# Schematic_DevKit_ESP32.net
KiCad netlist of a schematic drawn in Altium Designer
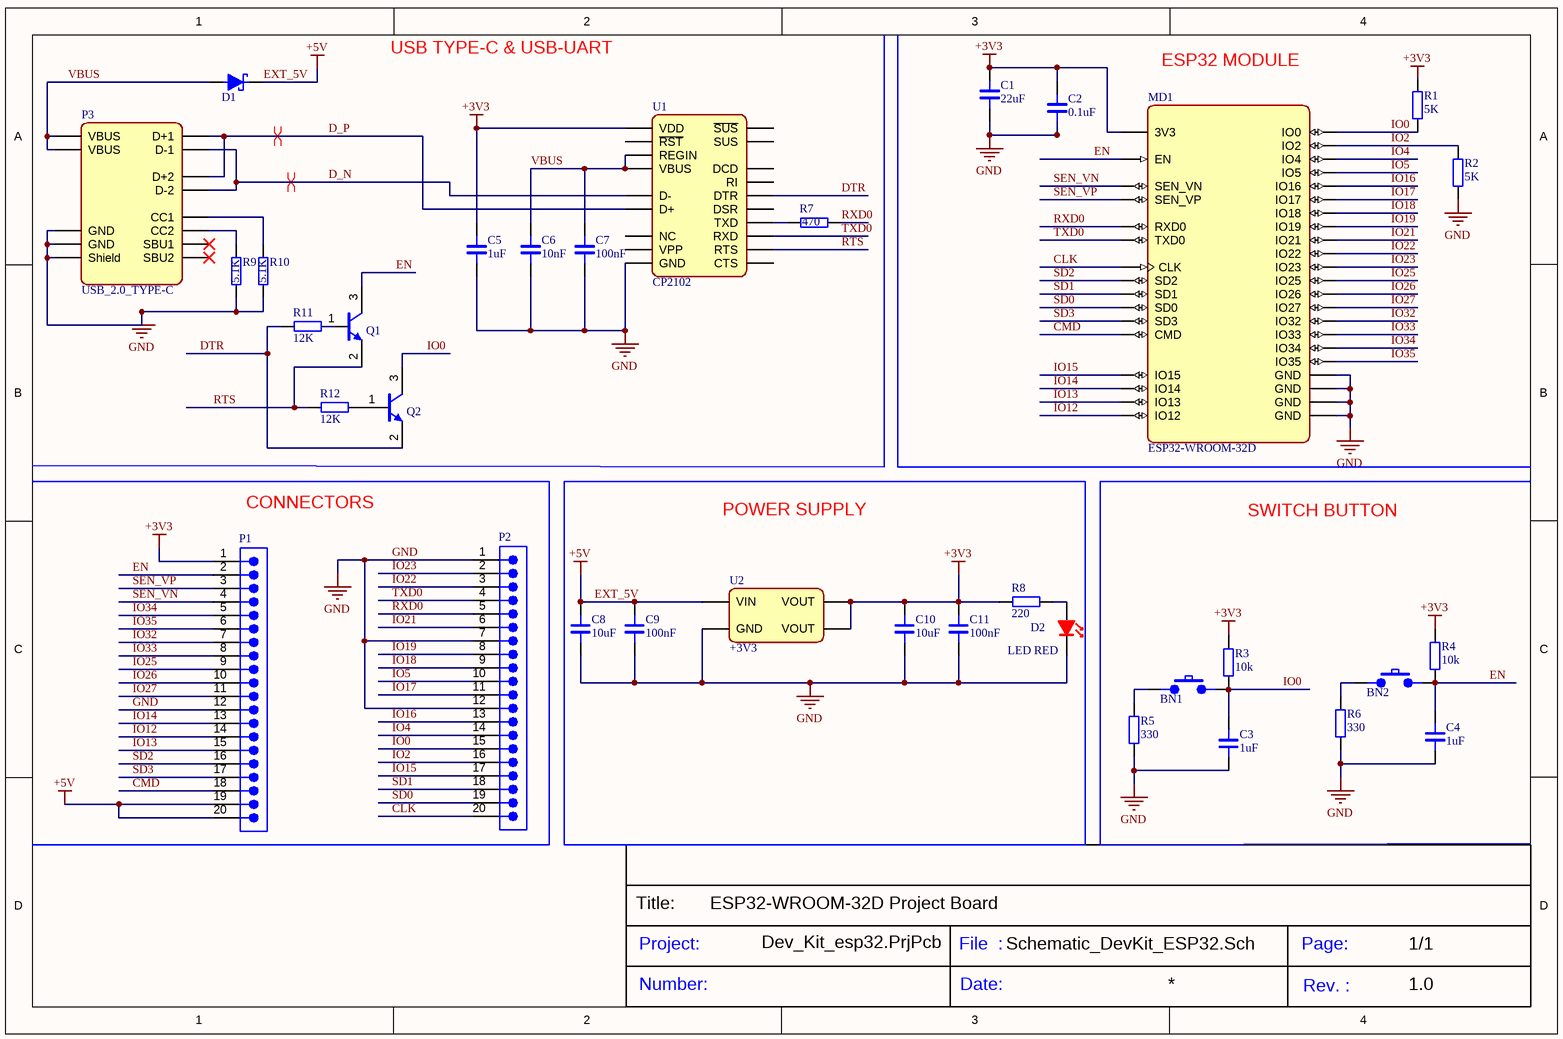
[diagram p0: Schematic_DevKit_ESP32.SchDoc]

(export (version "E")
  (design (tool "Eeschema 10.0.6"))
  (components
    (comp (ref "BN1")
      (value "SKRPABE010")
      (footprint "BTN_SKRPABE010")
      (description "3.2mm 2.5mm button 50mA Brick SPST 16V SMD Tactile Switches")
      (fields (field (name "JLCPCB PART") "?"))
      (libsource (lib "FIC_OAL") (part "BTN_SKRPABE010"))
    )
    (comp (ref "BN2")
      (value "SKRPABE010")
      (footprint "BTN_SKRPABE010")
      (description "3.2mm 2.5mm button 50mA Brick SPST 16V SMD Tactile Switches")
      (fields (field (name "JLCPCB PART") "?"))
      (libsource (lib "FIC_OAL") (part "BTN_SKRPABE010"))
    )
    (comp (ref "C1")
      (value "22uF")
      (footprint "CAP_0603")
      (description "0603 Multilayer Ceramic Capacitors MLCC - SMD/SMT ROHS")
      (fields (field (name "LCSC PART") "C86295") (field (name "JLCPCB PART") "?"))
      (libsource (lib "FIC_OAL") (part "CAP_0603"))
    )
    (comp (ref "C2")
      (value "0.1uF")
      (footprint "CAP_0603")
      (description "0603 Multilayer Ceramic Capacitors MLCC - SMD/SMT ROHS")
      (fields (field (name "LCSC PART") "C36911391") (field (name "JLCPCB PART") "?"))
      (libsource (lib "FIC_OAL") (part "CAP_0603"))
    )
    (comp (ref "C3")
      (value "1uF")
      (footprint "CAP_0603")
      (description "0603 Multilayer Ceramic Capacitors MLCC - SMD/SMT ROHS")
      (fields (field (name "LCSC PART") "C111590") (field (name "JLCPCB PART") "?"))
      (libsource (lib "FIC_OAL") (part "CAP_0603"))
    )
    (comp (ref "C4")
      (value "1uF")
      (footprint "CAP_0603")
      (description "0603 Multilayer Ceramic Capacitors MLCC - SMD/SMT ROHS")
      (fields (field (name "LCSC PART") "C111590") (field (name "JLCPCB PART") "?"))
      (libsource (lib "FIC_OAL") (part "CAP_0603"))
    )
    (comp (ref "C5")
      (value "1uF")
      (footprint "CAP_0603")
      (description "0603 Multilayer Ceramic Capacitors MLCC - SMD/SMT ROHS")
      (fields (field (name "LCSC PART") "C111590") (field (name "JLCPCB PART") "?"))
      (libsource (lib "FIC_OAL") (part "CAP_0603"))
    )
    (comp (ref "C6")
      (value "10nF")
      (footprint "CAP_0603")
      (description "0603 Multilayer Ceramic Capacitors MLCC - SMD/SMT ROHS")
      (fields (field (name "LCSC PART") "C36911415") (field (name "JLCPCB PART") "?"))
      (libsource (lib "FIC_OAL") (part "CAP_0603"))
    )
    (comp (ref "C7")
      (value "100nF")
      (footprint "CAP_0603")
      (description "0603 Multilayer Ceramic Capacitors MLCC - SMD/SMT ROHS")
      (fields (field (name "LCSC PART") "C519438") (field (name "JLCPCB PART") "?"))
      (libsource (lib "FIC_OAL") (part "CAP_0603"))
    )
    (comp (ref "C8")
      (value "10uF")
      (footprint "CAP_0603")
      (description "0603 Multilayer Ceramic Capacitors MLCC - SMD/SMT ROHS")
      (fields (field (name "LCSC PART") "C19702") (field (name "JLCPCB PART") "?"))
      (libsource (lib "FIC_OAL") (part "CAP_0603"))
    )
    (comp (ref "C9")
      (value "100nF")
      (footprint "CAP_0603")
      (description "0603 Multilayer Ceramic Capacitors MLCC - SMD/SMT ROHS")
      (fields (field (name "LCSC PART") "?"))
      (libsource (lib "FIC_OAL") (part "CAP_0603"))
    )
    (comp (ref "C10")
      (value "10uF")
      (footprint "CAP_0603")
      (description "0603 Multilayer Ceramic Capacitors MLCC - SMD/SMT ROHS")
      (fields (field (name "LCSC PART") "C19702") (field (name "JLCPCB PART") "?"))
      (libsource (lib "FIC_OAL") (part "CAP_0603"))
    )
    (comp (ref "C11")
      (value "100nF")
      (footprint "CAP_0603")
      (description "0603 Multilayer Ceramic Capacitors MLCC - SMD/SMT ROHS")
      (fields (field (name "LCSC PART") "?"))
      (libsource (lib "FIC_OAL") (part "CAP_0603"))
    )
    (comp (ref "D1")
      (value "SS34")
      (footprint "DIO_SMA")
      (description "40V 500mV@3A 3A SMC (SBD)")
      (fields (field (name "JLCPCB PART") "?") (field (name "LCSC PART") "C8678"))
      (libsource (lib "FIC_OAL") (part "DIO_SS34"))
    )
    (comp (ref "D2")
      (value "LED RED")
      (footprint "LED_RED_V0805")
      (description "20mA 615nm~630nm RED")
      (fields (field (name "JLCPCB PART") "?"))
      (libsource (lib "FIC_OAL") (part "LED_RED_V0805"))
    )
    (comp (ref "MD1")
      (value "ESP32-WROOM-32D")
      (footprint "MD_ESP32_WROOM_D")
      (description "core ESP32-D0WD, 32Mbits, 3.3V, 40Mhz, onboard antenna")
      (fields (field (name "MFR. PART") "ESP32-WROOM-32D-N4") (field (name "LCSC PART") "C473012"))
      (libsource (lib "FIC_OAL") (part "MD_ESP32_WROOM_D"))
    )
    (comp (ref "P1")
      (value "61302011121")
      (footprint "61302011121")
      (libsource (lib "Altium Content Vault") (part "Header_Male_1R_20P"))
    )
    (comp (ref "P2")
      (value "61302011121")
      (footprint "61302011121")
      (libsource (lib "Altium Content Vault") (part "Header_Male_1R_20P"))
    )
    (comp (ref "P3")
      (value "USB_2.0_TYPE-C")
      (footprint "CON_USB_2.0_TYPE-C")
      (description "USB Connectors USB Jack 2.0, Type-C, Horizontal SMT")
      (fields (field (name "MFR. PART") "GT-USB-7010ASV") (field (name "LCSC PART") "C2988369"))
      (libsource (lib "FIC_OAL") (part "CON_USB_2.0_TYPE-C"))
    )
    (comp (ref "Q1")
      (value "BC846x")
      (footprint "BJT_ BC846x")
      (description "Single Bipolar Transistor, NPN, 65 V, 100 mA, 250 mW, SOT23 (TO-236AB), 3 Pins, Surface Mount")
      (fields (field (name "MFR. PART") "BC846B") (field (name "LCSC PART") "C5338312"))
      (libsource (lib "FIC_OAL") (part "BJT_ BC846x"))
    )
    (comp (ref "Q2")
      (value "BC846x")
      (footprint "BJT_ BC846x")
      (description "Single Bipolar Transistor, NPN, 65 V, 100 mA, 250 mW, SOT23 (TO-236AB), 3 Pins, Surface Mount")
      (fields (field (name "MFR. PART") "BC846B") (field (name "LCSC PART") "C5338312"))
      (libsource (lib "FIC_OAL") (part "BJT_ BC846x"))
    )
    (comp (ref "R1")
      (value "5K")
      (footprint "RES_0603")
      (description "0603 Thick Film Resistor - Surface Mount ROHS")
      (fields (field (name "MFR. PART") "RTT035001FTP") (field (name "LCSC PART") "C166926"))
      (libsource (lib "FIC_OAL") (part "RES_0603"))
    )
    (comp (ref "R2")
      (value "5K")
      (footprint "RES_0603")
      (description "0603 Thick Film Resistor - Surface Mount ROHS")
      (fields (field (name "MFR. PART") "RTT035001FTP") (field (name "LCSC PART") "C166926"))
      (libsource (lib "FIC_OAL") (part "RES_0603"))
    )
    (comp (ref "R3")
      (value "10k")
      (footprint "RES_0603")
      (description "0603 Thick Film Resistor - Surface Mount ROHS")
      (fields (field (name "MFR. PART") "FRC0603J103 TS") (field (name "LCSC PART") "C2930027"))
      (libsource (lib "FIC_OAL") (part "RES_0603"))
    )
    (comp (ref "R4")
      (value "10k")
      (footprint "RES_0603")
      (description "0603 Thick Film Resistor - Surface Mount ROHS")
      (fields (field (name "MFR. PART") "FRC0603J103 TS") (field (name "LCSC PART") "C2930027"))
      (libsource (lib "FIC_OAL") (part "RES_0603"))
    )
    (comp (ref "R5")
      (value "330")
      (footprint "RES_0603")
      (description "0603 Thick Film Resistor - Surface Mount ROHS")
      (fields (field (name "MFR. PART") "0603WAJ0331T5E") (field (name "LCSC PART") "C25231"))
      (libsource (lib "FIC_OAL") (part "RES_0603"))
    )
    (comp (ref "R6")
      (value "330")
      (footprint "RES_0603")
      (description "0603 Thick Film Resistor - Surface Mount ROHS")
      (fields (field (name "MFR. PART") "?"))
      (libsource (lib "FIC_OAL") (part "RES_0603"))
    )
    (comp (ref "R7")
      (value "470")
      (footprint "RES_0603")
      (description "0603 Thick Film Resistor - Surface Mount ROHS")
      (fields (field (name "MFR. PART") "FRC0603F4700TS") (field (name "LCSC PART") "C2907041"))
      (libsource (lib "FIC_OAL") (part "RES_0603"))
    )
    (comp (ref "R8")
      (value "220")
      (footprint "RES_0603")
      (description "0603 Thick Film Resistor - Surface Mount ROHS")
      (fields (field (name "MFR. PART") "FRC0603F2200TS") (field (name "LCSC PART") "C2907014"))
      (libsource (lib "FIC_OAL") (part "RES_0603"))
    )
    (comp (ref "R9")
      (value "5.1K")
      (footprint "RES_0603")
      (description "0603 Thick Film Resistor - Surface Mount ROHS")
      (fields (field (name "MFR. PART") "FRC0603F5101TS") (field (name "LCSC PART") "C2907044"))
      (libsource (lib "FIC_OAL") (part "RES_0603"))
    )
    (comp (ref "R10")
      (value "5.1K")
      (footprint "RES_0603")
      (description "0603 Thick Film Resistor - Surface Mount ROHS")
      (fields (field (name "MFR. PART") "FRC0603F5101TS") (field (name "LCSC PART") "C2907044"))
      (libsource (lib "FIC_OAL") (part "RES_0603"))
    )
    (comp (ref "R11")
      (value "12K")
      (footprint "RES_0603")
      (description "0603 Thick Film Resistor - Surface Mount ROHS")
      (fields (field (name "MFR. PART") "FRC0603F1202TS") (field (name "LCSC PART") "C2906989"))
      (libsource (lib "FIC_OAL") (part "RES_0603"))
    )
    (comp (ref "R12")
      (value "12K")
      (footprint "RES_0603")
      (description "0603 Thick Film Resistor - Surface Mount ROHS")
      (fields (field (name "MFR. PART") "FRC0603F1202TS") (field (name "LCSC PART") "C2906989"))
      (libsource (lib "FIC_OAL") (part "RES_0603"))
    )
    (comp (ref "U1")
      (value "CP2102")
      (footprint "INF_CP2102")
      (description "USB to UART bridge USB 2.0 3.3V, CP2102-GMR, VFQFN-28")
      (fields (field (name "MFR. PART") "CP2102-GMR") (field (name "LCSC PART") "C6568"))
      (libsource (lib "FIC_OAL") (part "INF_CP2102"))
    )
    (comp (ref "U2")
      (value "+3V3")
      (footprint "PWR_LD1117_SOT223")
      (description "Linear Voltage Regulators (LDO)")
      (fields (field (name "MFR. PART") "LD1117-3.3") (field (name "LCSC PART") "C347229"))
      (libsource (lib "FIC_OAL") (part "PWR_LD1117"))
    )
  )
  (nets
    (net (code "1") (name "+3V3") (class "Default")
      (node (ref "C1") (pin "2") (pinfunction "2_2") (pintype "passive"))
      (node (ref "C10") (pin "2") (pinfunction "2_2") (pintype "passive"))
      (node (ref "C11") (pin "2") (pinfunction "2_2") (pintype "passive"))
      (node (ref "C2") (pin "2") (pinfunction "2_2") (pintype "passive"))
      (node (ref "C5") (pin "2") (pinfunction "2_2") (pintype "passive"))
      (node (ref "MD1") (pin "2") (pinfunction "3V3_2") (pintype "passive"))
      (node (ref "P1") (pin "1") (pinfunction "1_1") (pintype "passive"))
      (node (ref "R1") (pin "2") (pinfunction "2_2") (pintype "passive"))
      (node (ref "R3") (pin "2") (pinfunction "2_2") (pintype "passive"))
      (node (ref "R4") (pin "2") (pinfunction "2_2") (pintype "passive"))
      (node (ref "R8") (pin "1") (pinfunction "1_1") (pintype "passive"))
      (node (ref "U1") (pin "6") (pinfunction "VDD_6") (pintype "passive"))
      (node (ref "U2") (pin "2") (pinfunction "_VOUT_2") (pintype "passive"))
      (node (ref "U2") (pin "4") (pinfunction "VOUT_4") (pintype "passive"))
    )
    (net (code "2") (name "+5V") (class "Default")
      (node (ref "C8") (pin "2") (pinfunction "2_2") (pintype "passive"))
      (node (ref "C9") (pin "2") (pinfunction "2_2") (pintype "passive"))
      (node (ref "D1") (pin "C") (pinfunction "C_C") (pintype "passive"))
      (node (ref "P1") (pin "19") (pinfunction "19_19") (pintype "passive"))
      (node (ref "P1") (pin "20") (pinfunction "20_20") (pintype "passive"))
      (node (ref "U2") (pin "3") (pinfunction "VIN_3") (pintype "passive"))
    )
    (net (code "3") (name "/CLK") (class "Default")
      (node (ref "MD1") (pin "20") (pinfunction "CLK_20") (pintype "input"))
      (node (ref "P2") (pin "20") (pinfunction "20_20") (pintype "passive"))
    )
    (net (code "4") (name "/CMD") (class "Default")
      (node (ref "MD1") (pin "19") (pinfunction "CMD_19") (pintype "bidirectional"))
      (node (ref "P1") (pin "18") (pinfunction "18_18") (pintype "passive"))
    )
    (net (code "5") (name "/DTR") (class "Default")
      (node (ref "Q2") (pin "2") (pinfunction "E_2") (pintype "passive"))
      (node (ref "R11") (pin "1") (pinfunction "1_1") (pintype "passive"))
      (node (ref "U1") (pin "28") (pinfunction "DTR_28") (pintype "passive"))
    )
    (net (code "6") (name "/D_N") (class "Default")
      (node (ref "P3") (pin "A7") (pinfunction "D-1_A7") (pintype "passive"))
      (node (ref "P3") (pin "B7") (pinfunction "D-2_B7") (pintype "passive"))
      (node (ref "U1") (pin "5") (pinfunction "D-_5") (pintype "passive"))
    )
    (net (code "7") (name "/D_P") (class "Default")
      (node (ref "P3") (pin "A6") (pinfunction "D+1_A6") (pintype "passive"))
      (node (ref "P3") (pin "B6") (pinfunction "D+2_B6") (pintype "passive"))
      (node (ref "U1") (pin "4") (pinfunction "D+_4") (pintype "passive"))
    )
    (net (code "8") (name "/EN") (class "Default")
      (node (ref "BN2") (pin "34") (pinfunction "34_34") (pintype "passive"))
      (node (ref "C4") (pin "2") (pinfunction "2_2") (pintype "passive"))
      (node (ref "MD1") (pin "3") (pinfunction "EN_3") (pintype "input"))
      (node (ref "P1") (pin "2") (pinfunction "2_2") (pintype "passive"))
      (node (ref "Q1") (pin "3") (pinfunction "C_3") (pintype "passive"))
      (node (ref "R4") (pin "1") (pinfunction "1_1") (pintype "passive"))
    )
    (net (code "9") (name "/IO0") (class "Default")
      (node (ref "BN1") (pin "34") (pinfunction "34_34") (pintype "passive"))
      (node (ref "C3") (pin "2") (pinfunction "2_2") (pintype "passive"))
      (node (ref "MD1") (pin "25") (pinfunction "IO0_25") (pintype "bidirectional"))
      (node (ref "P2") (pin "15") (pinfunction "15_15") (pintype "passive"))
      (node (ref "Q2") (pin "3") (pinfunction "C_3") (pintype "passive"))
      (node (ref "R1") (pin "1") (pinfunction "1_1") (pintype "passive"))
      (node (ref "R3") (pin "1") (pinfunction "1_1") (pintype "passive"))
    )
    (net (code "10") (name "/IO2") (class "Default")
      (node (ref "MD1") (pin "24") (pinfunction "IO2_24") (pintype "bidirectional"))
      (node (ref "P2") (pin "16") (pinfunction "16_16") (pintype "passive"))
      (node (ref "R2") (pin "2") (pinfunction "2_2") (pintype "passive"))
    )
    (net (code "11") (name "/IO4") (class "Default")
      (node (ref "MD1") (pin "26") (pinfunction "IO4_26") (pintype "bidirectional"))
      (node (ref "P2") (pin "14") (pinfunction "14_14") (pintype "passive"))
    )
    (net (code "12") (name "/IO5") (class "Default")
      (node (ref "MD1") (pin "29") (pinfunction "IO5_29") (pintype "bidirectional"))
      (node (ref "P2") (pin "10") (pinfunction "10_10") (pintype "passive"))
    )
    (net (code "13") (name "/IO12") (class "Default")
      (node (ref "MD1") (pin "14") (pinfunction "IO12_14") (pintype "bidirectional"))
      (node (ref "P1") (pin "14") (pinfunction "14_14") (pintype "passive"))
    )
    (net (code "14") (name "/IO13") (class "Default")
      (node (ref "MD1") (pin "16") (pinfunction "IO13_16") (pintype "bidirectional"))
      (node (ref "P1") (pin "15") (pinfunction "15_15") (pintype "passive"))
    )
    (net (code "15") (name "/IO14") (class "Default")
      (node (ref "MD1") (pin "13") (pinfunction "IO14_13") (pintype "bidirectional"))
      (node (ref "P1") (pin "13") (pinfunction "13_13") (pintype "passive"))
    )
    (net (code "16") (name "/IO15") (class "Default")
      (node (ref "MD1") (pin "23") (pinfunction "IO15_23") (pintype "bidirectional"))
      (node (ref "P2") (pin "17") (pinfunction "17_17") (pintype "passive"))
    )
    (net (code "17") (name "/IO16") (class "Default")
      (node (ref "MD1") (pin "27") (pinfunction "IO16_27") (pintype "bidirectional"))
      (node (ref "P2") (pin "13") (pinfunction "13_13") (pintype "passive"))
    )
    (net (code "18") (name "/IO17") (class "Default")
      (node (ref "MD1") (pin "28") (pinfunction "IO17_28") (pintype "bidirectional"))
      (node (ref "P2") (pin "11") (pinfunction "11_11") (pintype "passive"))
    )
    (net (code "19") (name "/IO18") (class "Default")
      (node (ref "MD1") (pin "30") (pinfunction "IO18_30") (pintype "bidirectional"))
      (node (ref "P2") (pin "9") (pinfunction "9_9") (pintype "passive"))
    )
    (net (code "20") (name "/IO19") (class "Default")
      (node (ref "MD1") (pin "31") (pinfunction "IO19_31") (pintype "bidirectional"))
      (node (ref "P2") (pin "8") (pinfunction "8_8") (pintype "passive"))
    )
    (net (code "21") (name "/IO21") (class "Default")
      (node (ref "MD1") (pin "33") (pinfunction "IO21_33") (pintype "bidirectional"))
      (node (ref "P2") (pin "6") (pinfunction "6_6") (pintype "passive"))
    )
    (net (code "22") (name "/IO22") (class "Default")
      (node (ref "MD1") (pin "36") (pinfunction "IO22_36") (pintype "bidirectional"))
      (node (ref "P2") (pin "3") (pinfunction "3_3") (pintype "passive"))
    )
    (net (code "23") (name "/IO23") (class "Default")
      (node (ref "MD1") (pin "37") (pinfunction "IO23_37") (pintype "bidirectional"))
      (node (ref "P2") (pin "2") (pinfunction "2_2") (pintype "passive"))
    )
    (net (code "24") (name "/IO25") (class "Default")
      (node (ref "MD1") (pin "10") (pinfunction "IO25_10") (pintype "bidirectional"))
      (node (ref "P1") (pin "9") (pinfunction "9_9") (pintype "passive"))
    )
    (net (code "25") (name "/IO26") (class "Default")
      (node (ref "MD1") (pin "11") (pinfunction "IO26_11") (pintype "bidirectional"))
      (node (ref "P1") (pin "10") (pinfunction "10_10") (pintype "passive"))
    )
    (net (code "26") (name "/IO27") (class "Default")
      (node (ref "MD1") (pin "12") (pinfunction "IO27_12") (pintype "bidirectional"))
      (node (ref "P1") (pin "11") (pinfunction "11_11") (pintype "passive"))
    )
    (net (code "27") (name "/IO32") (class "Default")
      (node (ref "MD1") (pin "8") (pinfunction "IO32_8") (pintype "bidirectional"))
      (node (ref "P1") (pin "7") (pinfunction "7_7") (pintype "passive"))
    )
    (net (code "28") (name "/IO33") (class "Default")
      (node (ref "MD1") (pin "9") (pinfunction "IO33_9") (pintype "bidirectional"))
      (node (ref "P1") (pin "8") (pinfunction "8_8") (pintype "passive"))
    )
    (net (code "29") (name "/IO34") (class "Default")
      (node (ref "MD1") (pin "6") (pinfunction "IO34_6") (pintype "bidirectional"))
      (node (ref "P1") (pin "5") (pinfunction "5_5") (pintype "passive"))
    )
    (net (code "30") (name "/IO35") (class "Default")
      (node (ref "MD1") (pin "7") (pinfunction "IO35_7") (pintype "bidirectional"))
      (node (ref "P1") (pin "6") (pinfunction "6_6") (pintype "passive"))
    )
    (net (code "31") (name "/RTS") (class "Default")
      (node (ref "Q1") (pin "2") (pinfunction "E_2") (pintype "passive"))
      (node (ref "R12") (pin "1") (pinfunction "1_1") (pintype "passive"))
      (node (ref "U1") (pin "24") (pinfunction "RTS_24") (pintype "passive"))
    )
    (net (code "32") (name "/RXD0") (class "Default")
      (node (ref "MD1") (pin "34") (pinfunction "RXD0_34") (pintype "bidirectional"))
      (node (ref "P2") (pin "5") (pinfunction "5_5") (pintype "passive"))
      (node (ref "R7") (pin "2") (pinfunction "2_2") (pintype "passive"))
    )
    (net (code "33") (name "/SD0") (class "Default")
      (node (ref "MD1") (pin "21") (pinfunction "SD0_21") (pintype "bidirectional"))
      (node (ref "P2") (pin "19") (pinfunction "19_19") (pintype "passive"))
    )
    (net (code "34") (name "/SD1") (class "Default")
      (node (ref "MD1") (pin "22") (pinfunction "SD1_22") (pintype "bidirectional"))
      (node (ref "P2") (pin "18") (pinfunction "18_18") (pintype "passive"))
    )
    (net (code "35") (name "/SD2") (class "Default")
      (node (ref "MD1") (pin "17") (pinfunction "SD2_17") (pintype "bidirectional"))
      (node (ref "P1") (pin "16") (pinfunction "16_16") (pintype "passive"))
    )
    (net (code "36") (name "/SD3") (class "Default")
      (node (ref "MD1") (pin "18") (pinfunction "SD3_18") (pintype "bidirectional"))
      (node (ref "P1") (pin "17") (pinfunction "17_17") (pintype "passive"))
    )
    (net (code "37") (name "/SEN_VN") (class "Default")
      (node (ref "MD1") (pin "5") (pinfunction "SEN_VN_5") (pintype "bidirectional"))
      (node (ref "P1") (pin "4") (pinfunction "4_4") (pintype "passive"))
    )
    (net (code "38") (name "/SEN_VP") (class "Default")
      (node (ref "MD1") (pin "4") (pinfunction "SEN_VP_4") (pintype "bidirectional"))
      (node (ref "P1") (pin "3") (pinfunction "3_3") (pintype "passive"))
    )
    (net (code "39") (name "/TXD0") (class "Default")
      (node (ref "MD1") (pin "35") (pinfunction "TXD0_35") (pintype "bidirectional"))
      (node (ref "P2") (pin "4") (pinfunction "4_4") (pintype "passive"))
      (node (ref "U1") (pin "25") (pinfunction "RXD_25") (pintype "passive"))
    )
    (net (code "40") (name "/VBUS") (class "Default")
      (node (ref "C6") (pin "2") (pinfunction "2_2") (pintype "passive"))
      (node (ref "C7") (pin "2") (pinfunction "2_2") (pintype "passive"))
      (node (ref "D1") (pin "A") (pinfunction "A_A") (pintype "passive"))
      (node (ref "P3") (pin "A4/B9") (pinfunction "VBUS_A4/B9") (pintype "passive"))
      (node (ref "P3") (pin "A9/B4") (pinfunction "VBUS_A9/B4") (pintype "passive"))
      (node (ref "U1") (pin "7") (pinfunction "REGIN_7") (pintype "passive"))
      (node (ref "U1") (pin "8") (pinfunction "VBUS_8") (pintype "passive"))
    )
    (net (code "41") (name "GND") (class "Default")
      (node (ref "C1") (pin "1") (pinfunction "1_1") (pintype "passive"))
      (node (ref "C10") (pin "1") (pinfunction "1_1") (pintype "passive"))
      (node (ref "C11") (pin "1") (pinfunction "1_1") (pintype "passive"))
      (node (ref "C2") (pin "1") (pinfunction "1_1") (pintype "passive"))
      (node (ref "C3") (pin "1") (pinfunction "1_1") (pintype "passive"))
      (node (ref "C4") (pin "1") (pinfunction "1_1") (pintype "passive"))
      (node (ref "C5") (pin "1") (pinfunction "1_1") (pintype "passive"))
      (node (ref "C6") (pin "1") (pinfunction "1_1") (pintype "passive"))
      (node (ref "C7") (pin "1") (pinfunction "1_1") (pintype "passive"))
      (node (ref "C8") (pin "1") (pinfunction "1_1") (pintype "passive"))
      (node (ref "C9") (pin "1") (pinfunction "1_1") (pintype "passive"))
      (node (ref "D2") (pin "C") (pinfunction "1_C") (pintype "passive"))
      (node (ref "MD1") (pin "1") (pinfunction "GND_1") (pintype "passive"))
      (node (ref "MD1") (pin "15") (pinfunction "GND_15") (pintype "power_in"))
      (node (ref "MD1") (pin "38") (pinfunction "GND_38") (pintype "power_in"))
      (node (ref "MD1") (pin "39") (pinfunction "GND_39") (pintype "power_in"))
      (node (ref "P1") (pin "12") (pinfunction "12_12") (pintype "passive"))
      (node (ref "P2") (pin "1") (pinfunction "1_1") (pintype "passive"))
      (node (ref "P2") (pin "12") (pinfunction "12_12") (pintype "passive"))
      (node (ref "P2") (pin "7") (pinfunction "7_7") (pintype "passive"))
      (node (ref "P3") (pin "A1/B12") (pinfunction "GND_A1/B12") (pintype "passive"))
      (node (ref "P3") (pin "A12/B1") (pinfunction "GND_A12/B1") (pintype "passive"))
      (node (ref "P3") (pin "Shell") (pinfunction "Shield_Shell") (pintype "passive"))
      (node (ref "R10") (pin "1") (pinfunction "1_1") (pintype "passive"))
      (node (ref "R2") (pin "1") (pinfunction "1_1") (pintype "passive"))
      (node (ref "R5") (pin "1") (pinfunction "1_1") (pintype "passive"))
      (node (ref "R6") (pin "1") (pinfunction "1_1") (pintype "passive"))
      (node (ref "R9") (pin "1") (pinfunction "1_1") (pintype "passive"))
      (node (ref "U1") (pin "3") (pinfunction "GND_3") (pintype "passive"))
      (node (ref "U2") (pin "1") (pinfunction "GND_1") (pintype "passive"))
    )
    (net (code "42") (name "Net-(BN1-Pad12)") (class "Default")
      (node (ref "BN1") (pin "12") (pinfunction "12_12") (pintype "passive"))
      (node (ref "R5") (pin "2") (pinfunction "2_2") (pintype "passive"))
    )
    (net (code "43") (name "Net-(BN2-Pad12)") (class "Default")
      (node (ref "BN2") (pin "12") (pinfunction "12_12") (pintype "passive"))
      (node (ref "R6") (pin "2") (pinfunction "2_2") (pintype "passive"))
    )
    (net (code "44") (name "Net-(D2-2)") (class "Default")
      (node (ref "D2") (pin "A") (pinfunction "2_A") (pintype "passive"))
      (node (ref "R8") (pin "2") (pinfunction "2_2") (pintype "passive"))
    )
    (net (code "45") (name "Net-(P3-CC1)") (class "Default")
      (node (ref "P3") (pin "A5") (pinfunction "CC1_A5") (pintype "passive"))
      (node (ref "R10") (pin "2") (pinfunction "2_2") (pintype "passive"))
    )
    (net (code "46") (name "Net-(P3-CC2)") (class "Default")
      (node (ref "P3") (pin "B5") (pinfunction "CC2_B5") (pintype "passive"))
      (node (ref "R9") (pin "2") (pinfunction "2_2") (pintype "passive"))
    )
    (net (code "47") (name "Net-(Q1-B)") (class "Default")
      (node (ref "Q1") (pin "1") (pinfunction "B_1") (pintype "passive"))
      (node (ref "R11") (pin "2") (pinfunction "2_2") (pintype "passive"))
    )
    (net (code "48") (name "Net-(Q2-B)") (class "Default")
      (node (ref "Q2") (pin "1") (pinfunction "B_1") (pintype "passive"))
      (node (ref "R12") (pin "2") (pinfunction "2_2") (pintype "passive"))
    )
    (net (code "49") (name "Net-(U1-TXD)") (class "Default")
      (node (ref "R7") (pin "1") (pinfunction "1_1") (pintype "passive"))
      (node (ref "U1") (pin "26") (pinfunction "TXD_26") (pintype "passive"))
    )
    (net (code "50") (name "unconnected-(P3-SBU1-PadA8)") (class "Default")
      (node (ref "P3") (pin "A8") (pinfunction "SBU1_A8") (pintype "passive+no_connect"))
    )
    (net (code "51") (name "unconnected-(P3-SBU2-PadB8)") (class "Default")
      (node (ref "P3") (pin "B8") (pinfunction "SBU2_B8") (pintype "passive+no_connect"))
    )
    (net (code "52") (name "unconnected-(U1-CTS-Pad23)") (class "Default")
      (node (ref "U1") (pin "23") (pinfunction "CTS_23") (pintype "passive"))
    )
    (net (code "53") (name "unconnected-(U1-DCD-Pad1)") (class "Default")
      (node (ref "U1") (pin "1") (pinfunction "DCD_1") (pintype "passive"))
    )
    (net (code "54") (name "unconnected-(U1-DSR-Pad27)") (class "Default")
      (node (ref "U1") (pin "27") (pinfunction "DSR_27") (pintype "passive"))
    )
    (net (code "55") (name "unconnected-(U1-NC-Pad10)") (class "Default")
      (node (ref "U1") (pin "10") (pinfunction "NC_10") (pintype "passive"))
      (node (ref "U1") (pin "13") (pinfunction "NC_13") (pintype "passive"))
      (node (ref "U1") (pin "14") (pinfunction "NC_14") (pintype "passive"))
      (node (ref "U1") (pin "15") (pinfunction "NC_15") (pintype "passive"))
      (node (ref "U1") (pin "16") (pinfunction "NC_16") (pintype "passive"))
      (node (ref "U1") (pin "17") (pinfunction "NC_17") (pintype "passive"))
      (node (ref "U1") (pin "19") (pinfunction "NC_19") (pintype "passive"))
      (node (ref "U1") (pin "20") (pinfunction "NC_20") (pintype "passive"))
      (node (ref "U1") (pin "21") (pinfunction "NC_21") (pintype "passive"))
      (node (ref "U1") (pin "22") (pinfunction "NC_22") (pintype "passive"))
    )
    (net (code "56") (name "unconnected-(U1-RI-Pad2)") (class "Default")
      (node (ref "U1") (pin "2") (pinfunction "RI_2") (pintype "passive"))
    )
    (net (code "57") (name "unconnected-(U1-SUS-Pad12)") (class "Default")
      (node (ref "U1") (pin "12") (pinfunction "SUS_12") (pintype "passive"))
    )
    (net (code "58") (name "unconnected-(U1-VPP-Pad18)") (class "Default")
      (node (ref "U1") (pin "18") (pinfunction "VPP_18") (pintype "passive"))
    )
    (net (code "59") (name "unconnected-(U1-~{RST}-Pad9)") (class "Default")
      (node (ref "U1") (pin "9") (pinfunction "~{RST}_9") (pintype "passive"))
    )
    (net (code "60") (name "unconnected-(U1-~{SUS}-Pad11)") (class "Default")
      (node (ref "U1") (pin "11") (pinfunction "~{SUS}_11") (pintype "passive"))
    )
  )
)
